# Peripherals.net
KiCad netlist of a schematic drawn in Altium Designer
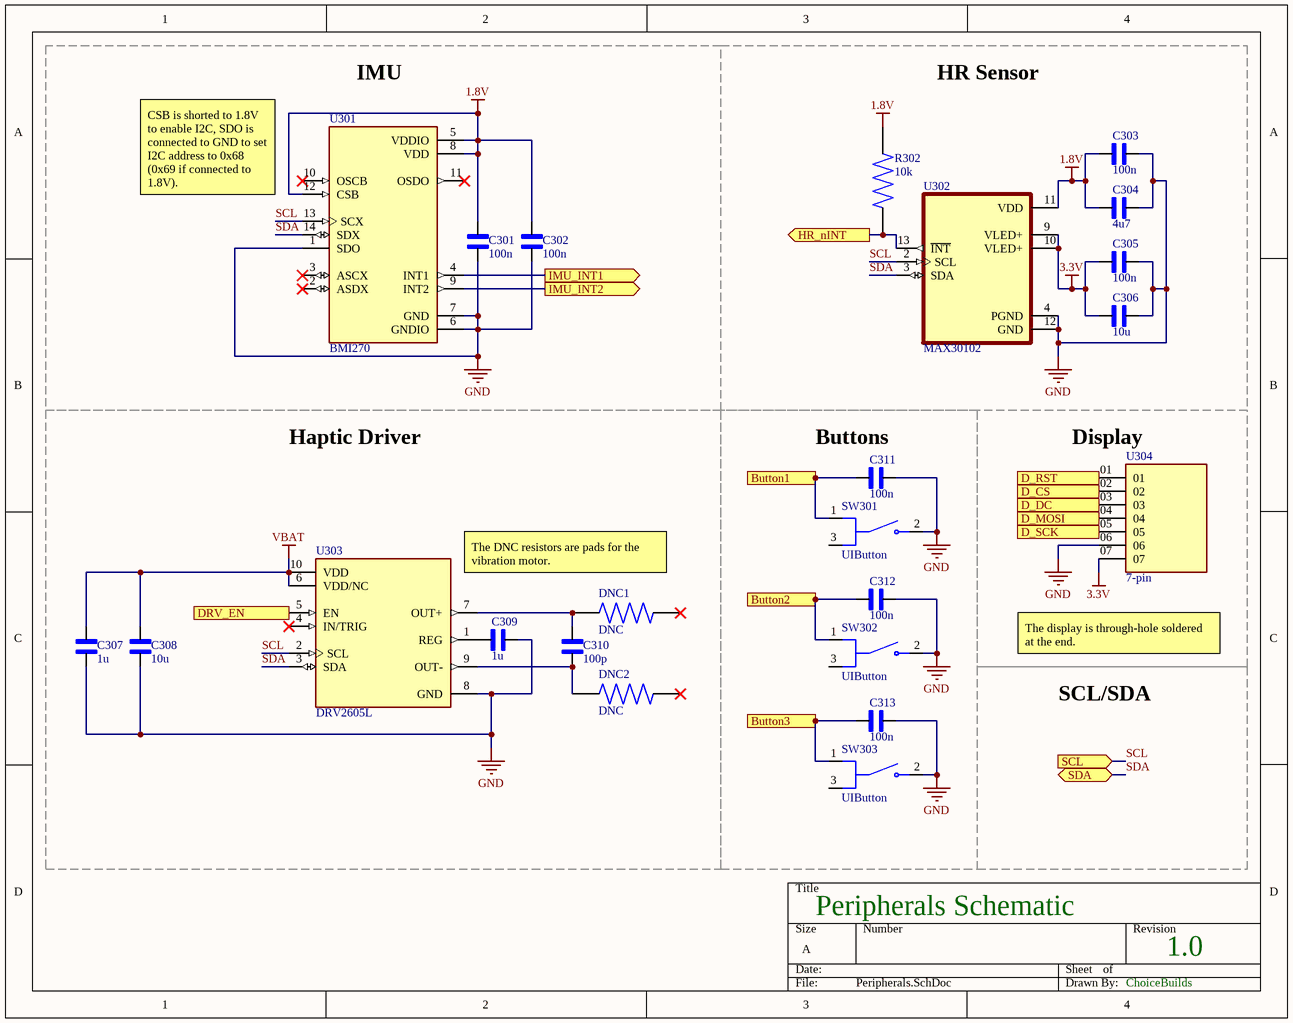
[diagram p0: Peripherals.SchDoc]

(export (version "E")
  (design (tool "Eeschema 10.0.6"))
  (components
    (comp (ref "C301") (value "100n") (footprint "0402c") (libsource (lib "") (part "0402c_1")))
    (comp (ref "C302") (value "100n") (footprint "0402c") (libsource (lib "") (part "0402c_1")))
    (comp (ref "C303") (value "100n") (footprint "0402c") (libsource (lib "UbiWatch_SchLib") (part "0402c")))
    (comp (ref "C304") (value "4u7") (footprint "0603c") (libsource (lib "") (part "0603c_1")))
    (comp (ref "C305") (value "100n") (footprint "0402c") (libsource (lib "UbiWatch_SchLib") (part "0402c")))
    (comp (ref "C306") (value "10u") (footprint "0603c") (libsource (lib "") (part "0603c_1")))
    (comp (ref "C307") (value "1u") (footprint "0402c") (libsource (lib "") (part "0402c_1")))
    (comp (ref "C308") (value "10u") (footprint "0402c") (libsource (lib "") (part "0402c_1")))
    (comp (ref "C309") (value "1u") (footprint "0603c") (libsource (lib "UbiWatch_SchLib") (part "0603c")))
    (comp (ref "C310") (value "100p") (footprint "0402c") (libsource (lib "") (part "0402c_1")))
    (comp (ref "C311") (value "100n") (footprint "0402c") (libsource (lib "") (part "0402c_2")))
    (comp (ref "C312") (value "100n") (footprint "0402c") (libsource (lib "") (part "0402c_2")))
    (comp (ref "C313") (value "100n") (footprint "0402c") (libsource (lib "") (part "0402c_2")))
    (comp (ref "DNC1") (value "DNC") (footprint "0805r") (libsource (lib "UbiWatch_SchLib") (part "0805r")))
    (comp (ref "DNC2") (value "DNC") (footprint "0805r") (libsource (lib "UbiWatch_SchLib") (part "0805r")))
    (comp (ref "R302") (value "10k") (footprint "0402r") (libsource (lib "UbiWatch_SchLib") (part "0402r")))
    (comp (ref "SW301")
      (value "UIButton")
      (footprint "TL3340AF160QG")
      (libsource (lib "JWatch_SchLib") (part "TL3340AF160QG"))
    )
    (comp (ref "SW302")
      (value "UIButton")
      (footprint "TL3340AF160QG")
      (libsource (lib "JWatch_SchLib") (part "TL3340AF160QG"))
    )
    (comp (ref "SW303")
      (value "UIButton")
      (footprint "TL3340AF160QG")
      (libsource (lib "JWatch_SchLib") (part "TL3340AF160QG"))
    )
    (comp (ref "U301")
      (value "BMI270")
      (footprint "BMI270")
      (libsource (lib "JWatch_SchLib") (part "BMI270"))
    )
    (comp (ref "U302")
      (value "MAX30102")
      (footprint "MAX30102")
      (libsource (lib "JWatch_SchLib") (part "MAX30102"))
    )
    (comp (ref "U303")
      (value "DRV2605L")
      (footprint "DRV2605L")
      (libsource (lib "JWatch_SchLib") (part "DRV2605L"))
    )
    (comp (ref "U304") (value "7-pin") (footprint "7-pin") (libsource (lib "UbiWatch_SchLib") (part "7-pin")))
  )
  (nets
    (net (code "1") (name "/Button1") (class "Default")
      (node (ref "C311") (pin "1") (pinfunction "1_1") (pintype "passive"))
      (node (ref "SW301") (pin "1") (pinfunction "COM_1_1") (pintype "passive"))
    )
    (net (code "2") (name "/Button2") (class "Default")
      (node (ref "C312") (pin "1") (pinfunction "1_1") (pintype "passive"))
      (node (ref "SW302") (pin "1") (pinfunction "COM_1_1") (pintype "passive"))
    )
    (net (code "3") (name "/Button3") (class "Default")
      (node (ref "C313") (pin "1") (pinfunction "1_1") (pintype "passive"))
      (node (ref "SW303") (pin "1") (pinfunction "COM_1_1") (pintype "passive"))
    )
    (net (code "4") (name "/DRV_EN") (class "Default")
      (node (ref "U303") (pin "5") (pinfunction "EN_5") (pintype "input"))
    )
    (net (code "5") (name "/D_CS") (class "Default")
      (node (ref "U304") (pin "02") (pinfunction "02_02") (pintype "passive"))
    )
    (net (code "6") (name "/D_DC") (class "Default")
      (node (ref "U304") (pin "03") (pinfunction "03_03") (pintype "passive"))
    )
    (net (code "7") (name "/D_MOSI") (class "Default")
      (node (ref "U304") (pin "04") (pinfunction "04_04") (pintype "passive"))
    )
    (net (code "8") (name "/D_RST") (class "Default")
      (node (ref "U304") (pin "01") (pinfunction "01_01") (pintype "passive"))
    )
    (net (code "9") (name "/D_SCK") (class "Default")
      (node (ref "U304") (pin "05") (pinfunction "05_05") (pintype "passive"))
    )
    (net (code "10") (name "/HR_nINT") (class "Default")
      (node (ref "R302") (pin "1") (pinfunction "1_1") (pintype "passive"))
      (node (ref "U302") (pin "13") (pinfunction "~{INT}_13") (pintype "output"))
    )
    (net (code "11") (name "/IMU_INT1") (class "Default")
      (node (ref "U301") (pin "4") (pinfunction "INT1_4") (pintype "output"))
    )
    (net (code "12") (name "/IMU_INT2") (class "Default")
      (node (ref "U301") (pin "9") (pinfunction "INT2_9") (pintype "output"))
    )
    (net (code "13") (name "/SCL") (class "Default")
      (node (ref "U301") (pin "13") (pinfunction "SCX_13") (pintype "input"))
      (node (ref "U302") (pin "2") (pinfunction "SCL_2") (pintype "input"))
      (node (ref "U303") (pin "2") (pinfunction "SCL_2") (pintype "input"))
    )
    (net (code "14") (name "/SDA") (class "Default")
      (node (ref "U301") (pin "14") (pinfunction "SDX_14") (pintype "bidirectional"))
      (node (ref "U302") (pin "3") (pinfunction "SDA_3") (pintype "bidirectional"))
      (node (ref "U303") (pin "3") (pinfunction "SDA_3") (pintype "bidirectional"))
    )
    (net (code "15") (name "1.8V") (class "Default")
      (node (ref "C301") (pin "2") (pinfunction "2_2") (pintype "passive"))
      (node (ref "C302") (pin "2") (pinfunction "2_2") (pintype "passive"))
      (node (ref "C303") (pin "2") (pinfunction "2_2") (pintype "passive"))
      (node (ref "C304") (pin "2") (pinfunction "2_2") (pintype "passive"))
      (node (ref "R302") (pin "2") (pinfunction "2_2") (pintype "passive"))
      (node (ref "U301") (pin "12") (pinfunction "CSB_12") (pintype "input"))
      (node (ref "U301") (pin "5") (pinfunction "VDDIO_5") (pintype "power_in"))
      (node (ref "U301") (pin "8") (pinfunction "VDD_8") (pintype "power_in"))
      (node (ref "U302") (pin "11") (pinfunction "VDD_11") (pintype "power_in"))
    )
    (net (code "16") (name "3.3V") (class "Default")
      (node (ref "C305") (pin "2") (pinfunction "2_2") (pintype "passive"))
      (node (ref "C306") (pin "2") (pinfunction "2_2") (pintype "passive"))
      (node (ref "U302") (pin "10") (pinfunction "VLED+_10") (pintype "power_in"))
      (node (ref "U302") (pin "9") (pinfunction "VLED+_9") (pintype "power_in"))
      (node (ref "U304") (pin "07") (pinfunction "07_07") (pintype "passive"))
    )
    (net (code "17") (name "GND") (class "Default")
      (node (ref "C301") (pin "1") (pinfunction "1_1") (pintype "passive"))
      (node (ref "C302") (pin "1") (pinfunction "1_1") (pintype "passive"))
      (node (ref "C303") (pin "1") (pinfunction "1_1") (pintype "passive"))
      (node (ref "C304") (pin "1") (pinfunction "1_1") (pintype "passive"))
      (node (ref "C305") (pin "1") (pinfunction "1_1") (pintype "passive"))
      (node (ref "C306") (pin "1") (pinfunction "1_1") (pintype "passive"))
      (node (ref "C307") (pin "1") (pinfunction "1_1") (pintype "passive"))
      (node (ref "C308") (pin "1") (pinfunction "1_1") (pintype "passive"))
      (node (ref "C309") (pin "2") (pinfunction "2_2") (pintype "passive"))
      (node (ref "C311") (pin "2") (pinfunction "2_2") (pintype "passive"))
      (node (ref "C312") (pin "2") (pinfunction "2_2") (pintype "passive"))
      (node (ref "C313") (pin "2") (pinfunction "2_2") (pintype "passive"))
      (node (ref "SW301") (pin "2") (pinfunction "NO_2") (pintype "passive"))
      (node (ref "SW302") (pin "2") (pinfunction "NO_2") (pintype "passive"))
      (node (ref "SW303") (pin "2") (pinfunction "NO_2") (pintype "passive"))
      (node (ref "U301") (pin "1") (pinfunction "SDO_1") (pintype "passive"))
      (node (ref "U301") (pin "6") (pinfunction "GNDIO_6") (pintype "power_in"))
      (node (ref "U301") (pin "7") (pinfunction "GND_7") (pintype "power_in"))
      (node (ref "U302") (pin "12") (pinfunction "GND_12") (pintype "power_in"))
      (node (ref "U302") (pin "4") (pinfunction "PGND_4") (pintype "power_in"))
      (node (ref "U303") (pin "8") (pinfunction "GND_8") (pintype "power_in"))
      (node (ref "U304") (pin "06") (pinfunction "06_06") (pintype "passive"))
    )
    (net (code "18") (name "Net-(U303-OUT+)") (class "Default")
      (node (ref "C310") (pin "2") (pinfunction "2_2") (pintype "passive"))
      (node (ref "DNC1") (pin "1") (pinfunction "1_1") (pintype "passive"))
      (node (ref "U303") (pin "7") (pinfunction "OUT+_7") (pintype "output"))
    )
    (net (code "19") (name "Net-(U303-OUT-)") (class "Default")
      (node (ref "C310") (pin "1") (pinfunction "1_1") (pintype "passive"))
      (node (ref "DNC2") (pin "1") (pinfunction "1_1") (pintype "passive"))
      (node (ref "U303") (pin "9") (pinfunction "OUT-_9") (pintype "output"))
    )
    (net (code "20") (name "Net-(U303-REG)") (class "Default")
      (node (ref "C309") (pin "1") (pinfunction "1_1") (pintype "passive"))
      (node (ref "U303") (pin "1") (pinfunction "REG_1") (pintype "output"))
    )
    (net (code "21") (name "VBAT") (class "Default")
      (node (ref "C307") (pin "2") (pinfunction "2_2") (pintype "passive"))
      (node (ref "C308") (pin "2") (pinfunction "2_2") (pintype "passive"))
      (node (ref "U303") (pin "10") (pinfunction "VDD_10") (pintype "power_in"))
      (node (ref "U303") (pin "6") (pinfunction "VDD/NC_6") (pintype "power_in"))
    )
    (net (code "22") (name "unconnected-(DNC1-Pad2)") (class "Default")
      (node (ref "DNC1") (pin "2") (pinfunction "2_2") (pintype "passive+no_connect"))
    )
    (net (code "23") (name "unconnected-(DNC2-Pad2)") (class "Default")
      (node (ref "DNC2") (pin "2") (pinfunction "2_2") (pintype "passive+no_connect"))
    )
    (net (code "24") (name "unconnected-(SW301-COM_2-Pad3)") (class "Default")
      (node (ref "SW301") (pin "3") (pinfunction "COM_2_3") (pintype "passive"))
    )
    (net (code "25") (name "unconnected-(SW302-COM_2-Pad3)") (class "Default")
      (node (ref "SW302") (pin "3") (pinfunction "COM_2_3") (pintype "passive"))
    )
    (net (code "26") (name "unconnected-(SW303-COM_2-Pad3)") (class "Default")
      (node (ref "SW303") (pin "3") (pinfunction "COM_2_3") (pintype "passive"))
    )
    (net (code "27") (name "unconnected-(U301-ASCX-Pad3)") (class "Default")
      (node (ref "U301") (pin "3") (pinfunction "ASCX_3") (pintype "bidirectional+no_connect"))
    )
    (net (code "28") (name "unconnected-(U301-ASDX-Pad2)") (class "Default")
      (node (ref "U301") (pin "2") (pinfunction "ASDX_2") (pintype "bidirectional+no_connect"))
    )
    (net (code "29") (name "unconnected-(U301-OSCB-Pad10)") (class "Default")
      (node (ref "U301") (pin "10") (pinfunction "OSCB_10") (pintype "input+no_connect"))
    )
    (net (code "30") (name "unconnected-(U301-OSDO-Pad11)") (class "Default")
      (node (ref "U301") (pin "11") (pinfunction "OSDO_11") (pintype "output+no_connect"))
    )
    (net (code "31") (name "unconnected-(U303-IN{slash}TRIG-Pad4)") (class "Default")
      (node (ref "U303") (pin "4") (pinfunction "IN/TRIG_4") (pintype "input+no_connect"))
    )
  )
)
